# OSO-MISC-20-024_Ring_USB_Adapter.net
KiCad netlist of a schematic drawn in EAGLE
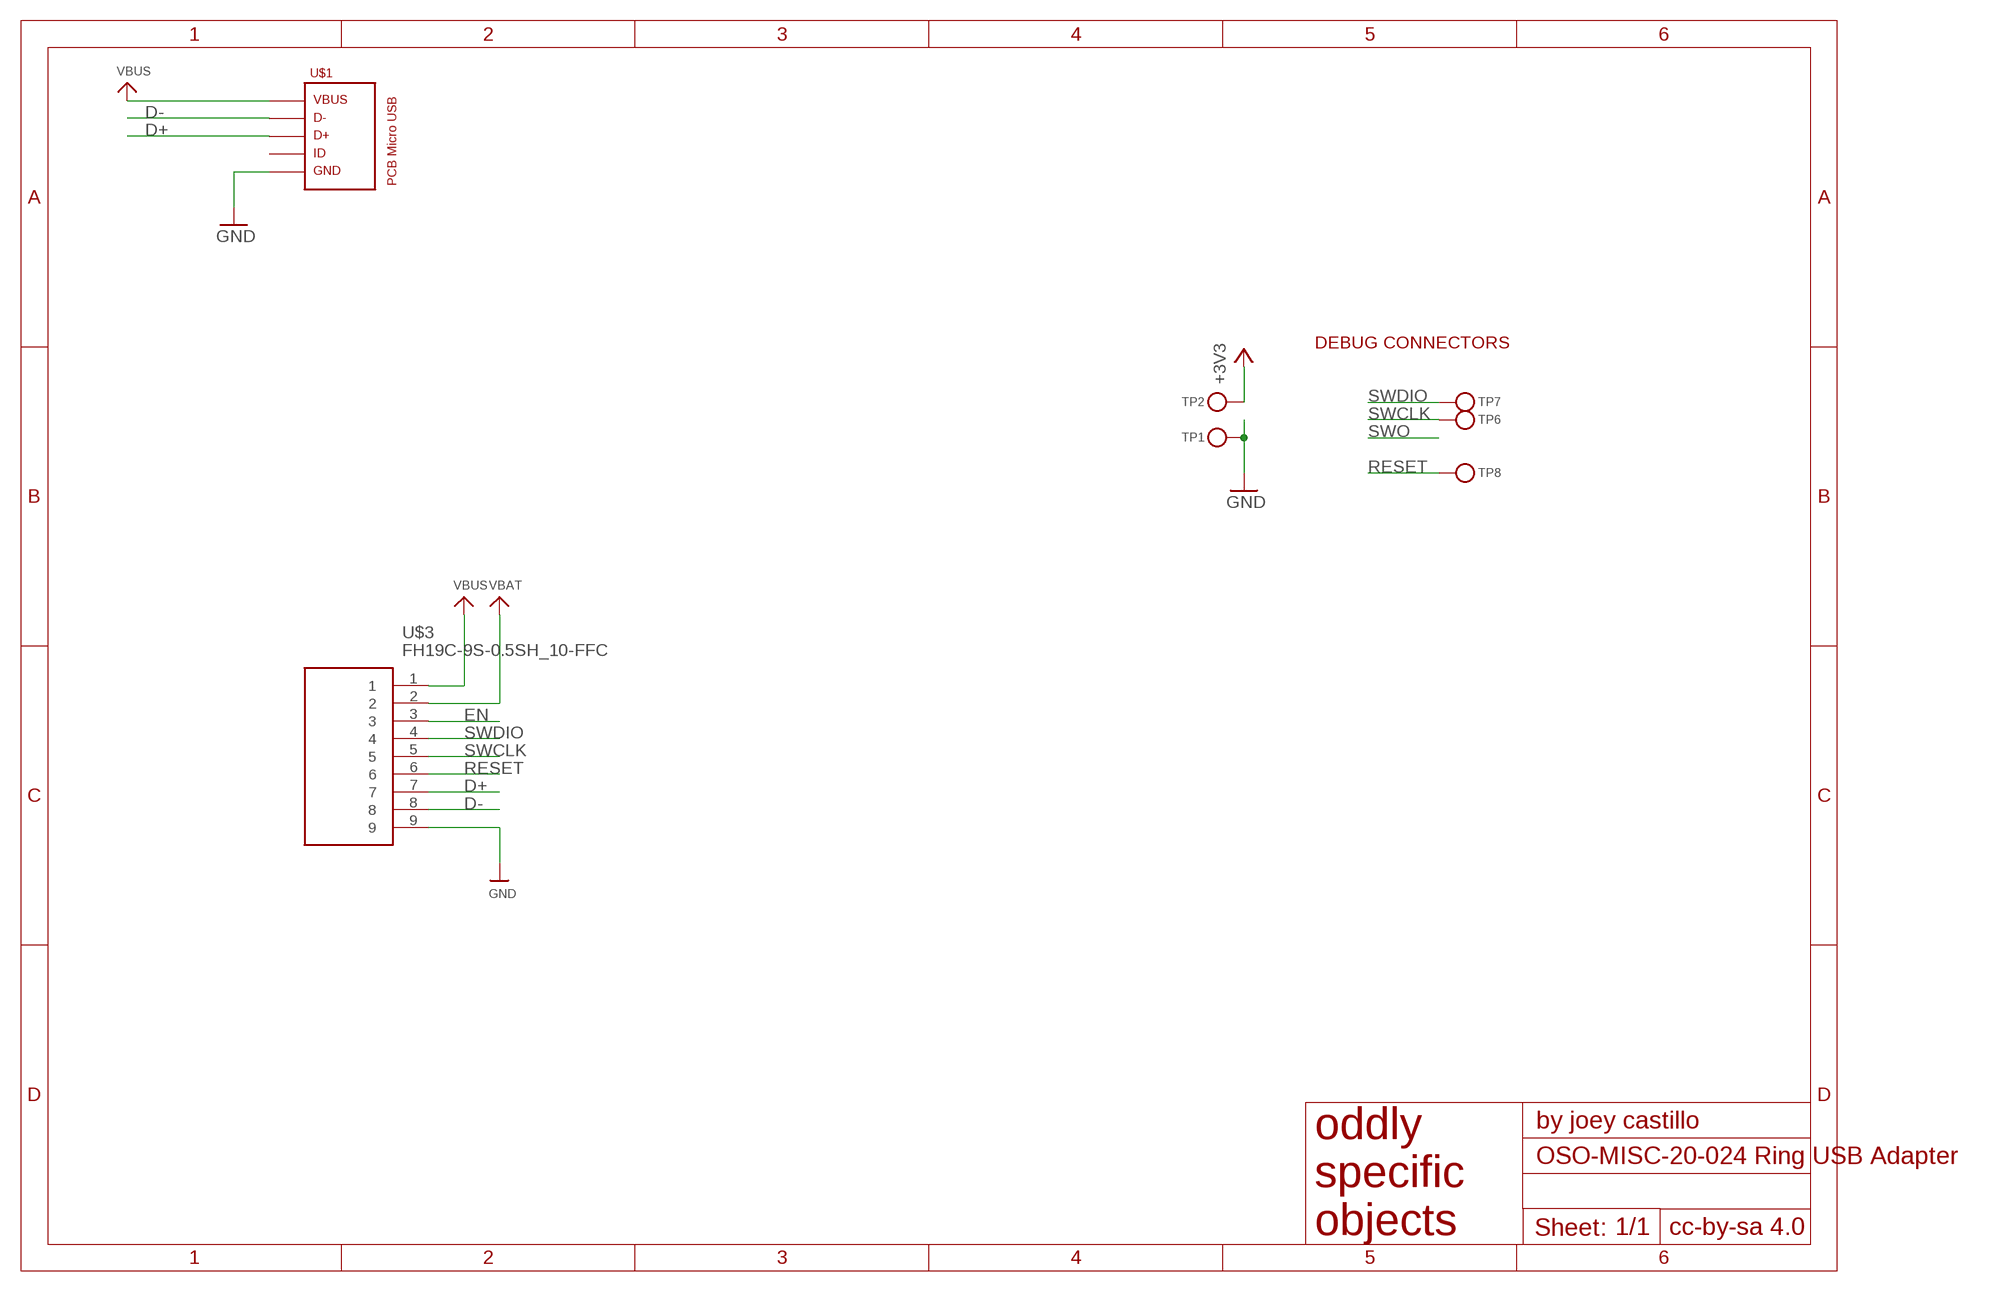
[diagram p0: schematic, sheet 1]

(export (version "E")
  (design (tool "Eeschema 10.0.6"))
  (components
    (comp (ref "TP1")
      (value "TESTPOINTROUND2MMNO")
      (footprint "eagle-import:TESTPOINT_ROUND_2MM_NO")
      (libsource (lib "eagle-import") (part "TESTPOINTROUND2MMNO"))
    )
    (comp (ref "TP2")
      (value "TESTPOINTROUND2MMNO")
      (footprint "eagle-import:TESTPOINT_ROUND_2MM_NO")
      (libsource (lib "eagle-import") (part "TESTPOINTROUND2MMNO"))
    )
    (comp (ref "TP6")
      (value "TESTPOINTROUND2MMNO")
      (footprint "eagle-import:TESTPOINT_ROUND_2MM_NO")
      (libsource (lib "eagle-import") (part "TESTPOINTROUND2MMNO"))
    )
    (comp (ref "TP7")
      (value "TESTPOINTROUND2MMNO")
      (footprint "eagle-import:TESTPOINT_ROUND_2MM_NO")
      (libsource (lib "eagle-import") (part "TESTPOINTROUND2MMNO"))
    )
    (comp (ref "TP8")
      (value "TESTPOINTROUND2MMNO")
      (footprint "eagle-import:TESTPOINT_ROUND_2MM_NO")
      (libsource (lib "eagle-import") (part "TESTPOINTROUND2MMNO"))
    )
    (comp (ref "U$1")
      (value "PCB_MICRO_USB_BSS_100")
      (footprint "eagle-import:USB_TYPE_B_SS_100")
      (libsource (lib "eagle-import") (part "PCB_MICRO_USB_BSS_100"))
    )
    (comp (ref "U$3")
      (value "FH19C-9S-0.5SH_10-FFC")
      (footprint "eagle-import:FH19C9S05SH10-FFC")
      (libsource (lib "eagle-import") (part "FH19C-9S-0.5SH_10-FFC"))
    )
  )
  (nets
    (net (code "1") (name "+3V3") (class "Default")
      (node (ref "TP2") (pin "P$1") (pinfunction "P$1_P$1") (pintype "bidirectional"))
    )
    (net (code "2") (name "/D+") (class "Default")
      (node (ref "U$1") (pin "3") (pinfunction "3_3") (pintype "bidirectional"))
      (node (ref "U$3") (pin "7") (pinfunction "7_7") (pintype "bidirectional"))
    )
    (net (code "3") (name "/D-") (class "Default")
      (node (ref "U$1") (pin "2") (pinfunction "2_2") (pintype "bidirectional"))
      (node (ref "U$3") (pin "8") (pinfunction "8_8") (pintype "bidirectional"))
    )
    (net (code "4") (name "/EN") (class "Default")
      (node (ref "U$3") (pin "3") (pinfunction "3_3") (pintype "bidirectional"))
    )
    (net (code "5") (name "/RESET") (class "Default")
      (node (ref "TP8") (pin "P$1") (pinfunction "P$1_P$1") (pintype "bidirectional"))
      (node (ref "U$3") (pin "6") (pinfunction "6_6") (pintype "bidirectional"))
    )
    (net (code "6") (name "/SWCLK") (class "Default")
      (node (ref "TP6") (pin "P$1") (pinfunction "P$1_P$1") (pintype "bidirectional"))
      (node (ref "U$3") (pin "5") (pinfunction "5_5") (pintype "bidirectional"))
    )
    (net (code "7") (name "/SWDIO") (class "Default")
      (node (ref "TP7") (pin "P$1") (pinfunction "P$1_P$1") (pintype "bidirectional"))
      (node (ref "U$3") (pin "4") (pinfunction "4_4") (pintype "bidirectional"))
    )
    (net (code "9") (name "GND") (class "Default")
      (node (ref "TP1") (pin "P$1") (pinfunction "P$1_P$1") (pintype "bidirectional"))
      (node (ref "U$1") (pin "5") (pinfunction "5_5") (pintype "bidirectional"))
      (node (ref "U$3") (pin "9") (pinfunction "9_9") (pintype "bidirectional"))
    )
    (net (code "10") (name "VBAT") (class "Default")
      (node (ref "U$3") (pin "2") (pinfunction "2_2") (pintype "bidirectional"))
    )
    (net (code "11") (name "VBUS") (class "Default")
      (node (ref "U$1") (pin "1") (pinfunction "1_1") (pintype "bidirectional"))
      (node (ref "U$3") (pin "1") (pinfunction "1_1") (pintype "bidirectional"))
    )
    (net (code "12") (name "unconnected-(U$1-Pad4)") (class "Default")
      (node (ref "U$1") (pin "4") (pinfunction "4_4") (pintype "bidirectional"))
    )
  )
)
